# Power.net
KiCad netlist of a schematic drawn in Altium Designer
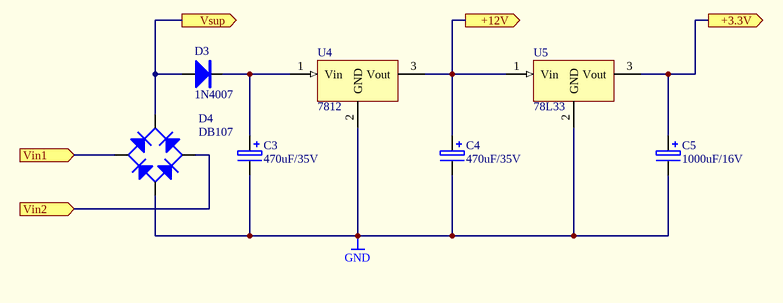
[diagram p0: Power.SchDoc]

(export (version "E")
  (design (tool "Eeschema 10.0.6"))
  (components
    (comp (ref "C3")
      (value "470uF/35V")
      (footprint "EC10x20")
      (description "Electrolytic Capacitor")
      (libsource (lib "*") (part "ELECTRO1"))
    )
    (comp (ref "C4")
      (value "470uF/35V")
      (footprint "EC8x16")
      (description "Electrolytic Capacitor")
      (libsource (lib "*") (part "ELECTRO1"))
    )
    (comp (ref "C5")
      (value "1000uF/16V")
      (footprint "EC6.3x12")
      (description "Electrolytic Capacitor")
      (libsource (lib "*") (part "ELECTRO1"))
    )
    (comp (ref "D3")
      (value "1N4007")
      (footprint "R400_V")
      (description "Diode")
      (libsource (lib "*") (part "DIODE"))
    )
    (comp (ref "D4") (value "DB107") (footprint "BRIDGE_PTH") (libsource (lib "*") (part "BRIDGE")))
    (comp (ref "U4") (value "7812") (footprint "TO-220-V") (libsource (lib "*") (part "78XX")))
    (comp (ref "U5") (value "78L33") (footprint "IC_TO-92") (libsource (lib "*") (part "78XX")))
  )
  (nets
    (net (code "1") (name "/+3.3V") (class "Default")
      (node (ref "C5") (pin "1") (pinfunction "1_1") (pintype "passive"))
      (node (ref "U5") (pin "3") (pinfunction "Vout_3") (pintype "power_in"))
    )
    (net (code "2") (name "/+12V") (class "Default")
      (node (ref "C4") (pin "1") (pinfunction "1_1") (pintype "passive"))
      (node (ref "U4") (pin "3") (pinfunction "Vout_3") (pintype "power_in"))
      (node (ref "U5") (pin "1") (pinfunction "Vin_1") (pintype "input"))
    )
    (net (code "3") (name "/Vin1") (class "Default")
      (node (ref "D4") (pin "1") (pinfunction "AC1_1") (pintype "passive"))
    )
    (net (code "4") (name "/Vin2") (class "Default")
      (node (ref "D4") (pin "2") (pinfunction "AC2_2") (pintype "passive"))
    )
    (net (code "5") (name "/Vsup") (class "Default")
      (node (ref "D3") (pin "1") (pinfunction "A_1") (pintype "passive"))
      (node (ref "D4") (pin "3") (pinfunction "P_3") (pintype "passive"))
    )
    (net (code "6") (name "GND") (class "Default")
      (node (ref "C3") (pin "2") (pinfunction "2_2") (pintype "passive"))
      (node (ref "C4") (pin "2") (pinfunction "2_2") (pintype "passive"))
      (node (ref "C5") (pin "2") (pinfunction "2_2") (pintype "passive"))
      (node (ref "D4") (pin "4") (pinfunction "M_4") (pintype "passive"))
      (node (ref "U4") (pin "2") (pinfunction "GND_2") (pintype "passive"))
      (node (ref "U5") (pin "2") (pinfunction "GND_2") (pintype "passive"))
    )
    (net (code "7") (name "Net-(D3-K)") (class "Default")
      (node (ref "C3") (pin "1") (pinfunction "1_1") (pintype "passive"))
      (node (ref "D3") (pin "2") (pinfunction "K_2") (pintype "passive"))
      (node (ref "U4") (pin "1") (pinfunction "Vin_1") (pintype "input"))
    )
  )
)
